# FPGA.net
KiCad netlist of a schematic drawn in Altium Designer
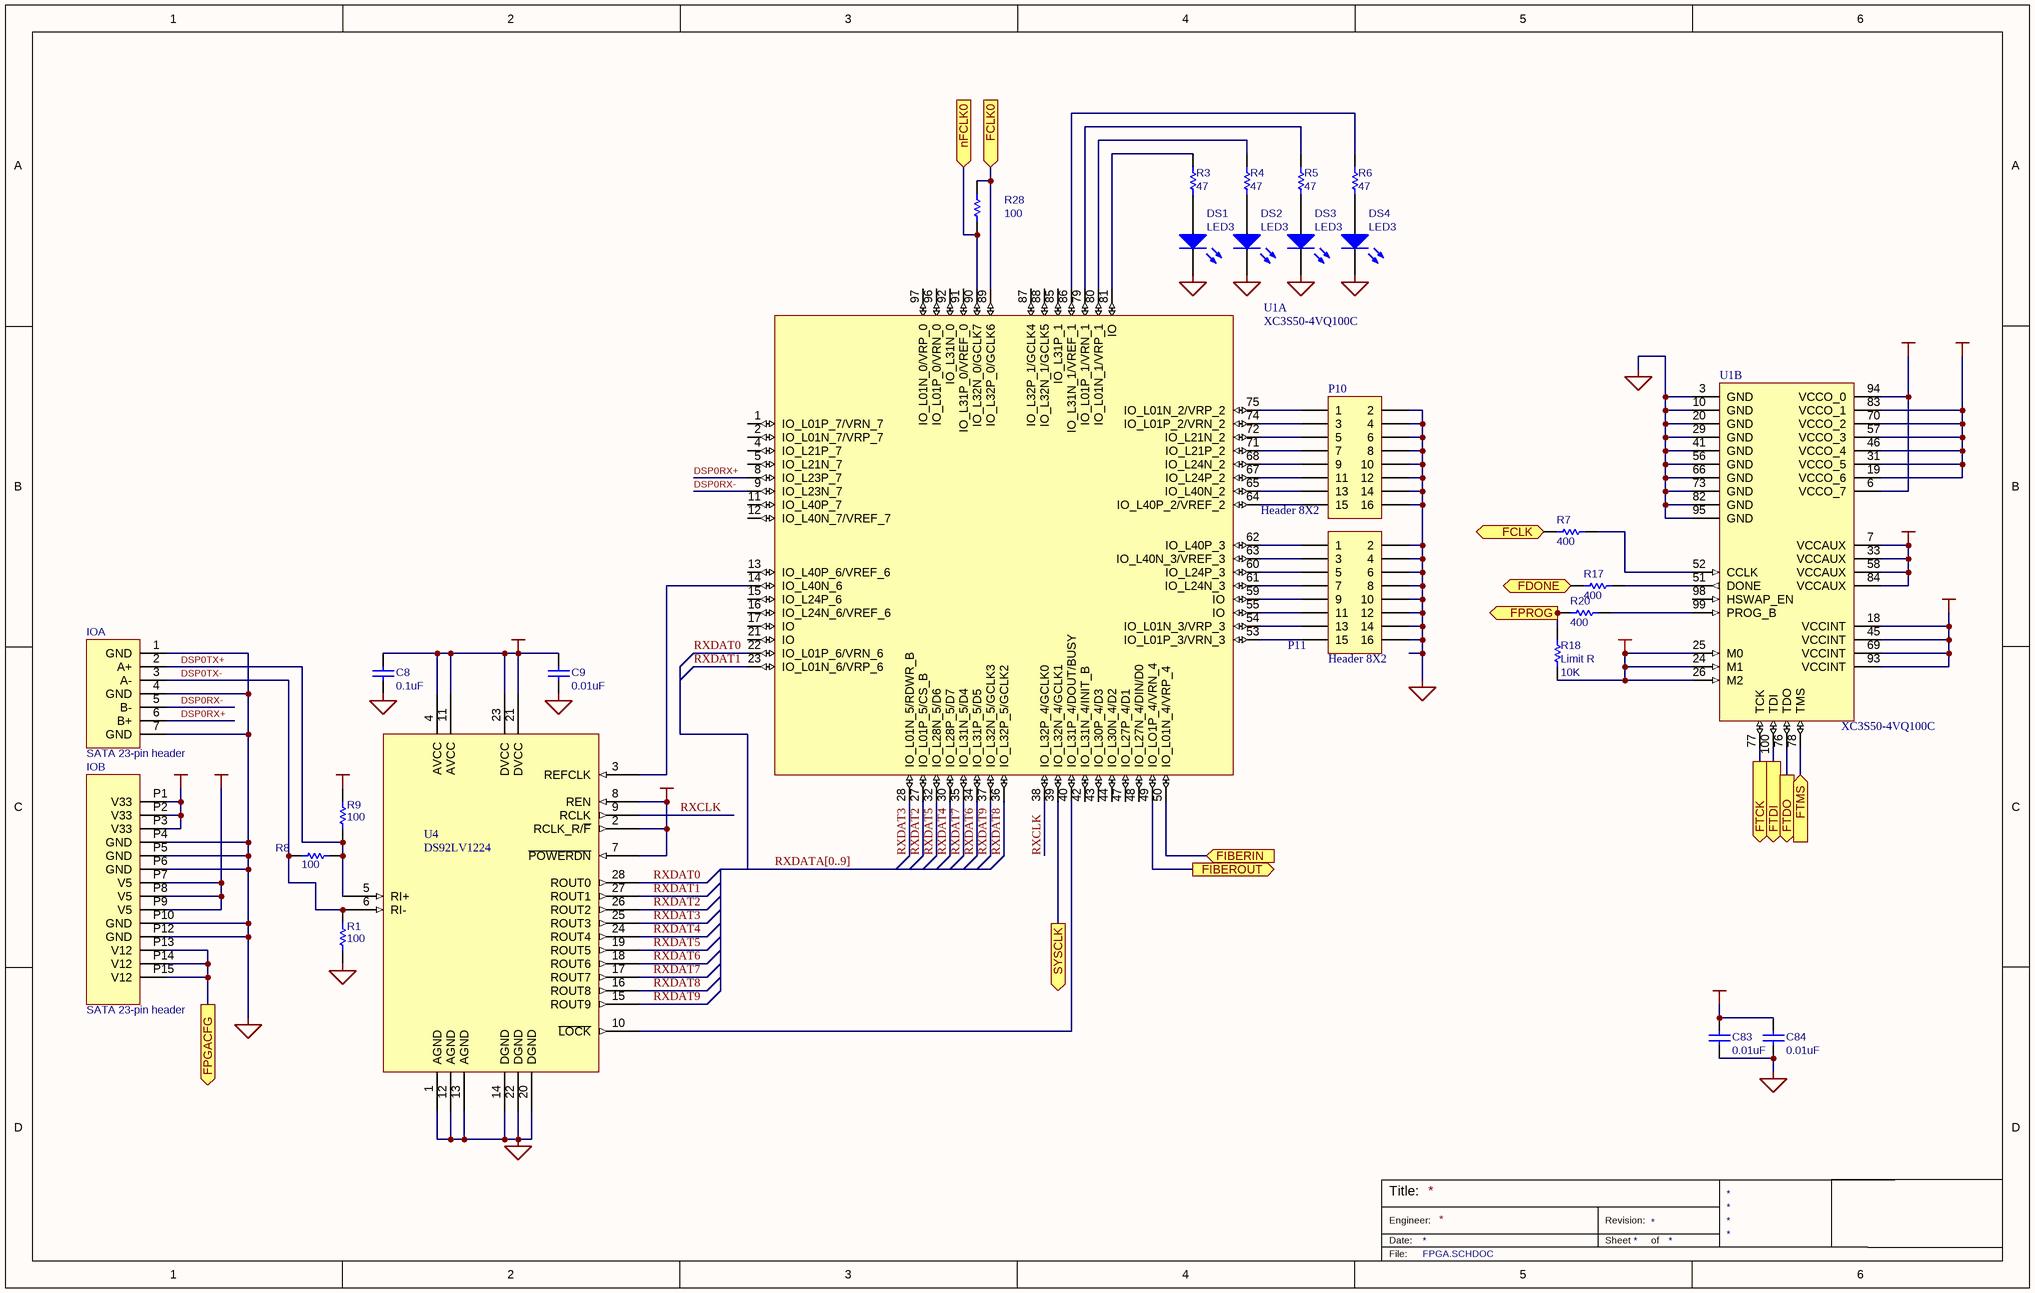
[diagram p0: FPGA.SCHDOC]

(export (version "E")
  (design (tool "Eeschema 10.0.6"))
  (components
    (comp (ref "C8")
      (value "0.1uF")
      (footprint "CC1005-0402")
      (description "Capacitor")
      (fields
        (field (name "MANUFACTURER") "Generic Components")
        (field (name "Comment") "Cap")
        (field (name "PUBLISHER") "Altium Limited")
      )
      (libsource (lib "Miscellaneous Devices") (part "Cap"))
    )
    (comp (ref "C9")
      (value "0.01uF")
      (footprint "CC1005-0402")
      (description "Capacitor")
      (fields
        (field (name "MANUFACTURER") "Generic Components")
        (field (name "Comment") "Cap")
        (field (name "PUBLISHER") "Altium Limited")
      )
      (libsource (lib "Miscellaneous Devices") (part "Cap"))
    )
    (comp (ref "C83")
      (value "0.01uF")
      (footprint "CC1005-0402")
      (description "Capacitor")
      (fields
        (field (name "MANUFACTURER") "Generic Components")
        (field (name "Comment") "Cap")
        (field (name "PUBLISHER") "Altium Limited")
      )
      (libsource (lib "Miscellaneous Devices") (part "Cap"))
    )
    (comp (ref "C84")
      (value "0.01uF")
      (footprint "CC1005-0402")
      (description "Capacitor")
      (fields
        (field (name "MANUFACTURER") "Generic Components")
        (field (name "Comment") "Cap")
        (field (name "PUBLISHER") "Altium Limited")
      )
      (libsource (lib "Miscellaneous Devices") (part "Cap"))
    )
    (comp (ref "DS1")
      (value "LED3")
      (footprint "SMD _LED")
      (description "Typical BLUE SiC LED")
      (fields (field (name "PUBLISHER") "Altium Limited"))
      (libsource (lib "Miscellaneous Devices") (part "LED3"))
    )
    (comp (ref "DS2")
      (value "LED3")
      (footprint "SMD _LED")
      (description "Typical BLUE SiC LED")
      (fields (field (name "PUBLISHER") "Altium Limited"))
      (libsource (lib "Miscellaneous Devices") (part "LED3"))
    )
    (comp (ref "DS3")
      (value "LED3")
      (footprint "SMD _LED")
      (description "Typical BLUE SiC LED")
      (fields (field (name "PUBLISHER") "Altium Limited"))
      (libsource (lib "Miscellaneous Devices") (part "LED3"))
    )
    (comp (ref "DS4")
      (value "LED3")
      (footprint "SMD _LED")
      (description "Typical BLUE SiC LED")
      (fields (field (name "PUBLISHER") "Altium Limited"))
      (libsource (lib "Miscellaneous Devices") (part "LED3"))
    )
    (comp (ref "IO")
      (value "SATA 23-pin header")
      (footprint "MOLEX 87703-0001")
      (libsource (lib "parts") (part "SATA-23"))
    )
    (comp (ref "P10")
      (value "Header 8X2")
      (footprint "HDR2X8")
      (description "Header, 8-Pin, Dual row")
      (fields (field (name "PUBLISHER") "Altium Limited"))
      (libsource (lib "Miscellaneous Connectors") (part "Header 8X2"))
    )
    (comp (ref "P11")
      (value "Header 8X2")
      (footprint "HDR2X8")
      (description "Header, 8-Pin, Dual row")
      (fields (field (name "PUBLISHER") "Altium Limited"))
      (libsource (lib "Miscellaneous Connectors") (part "Header 8X2"))
    )
    (comp (ref "R1")
      (value "100")
      (footprint "CR1005-0402")
      (description "Resistor")
      (fields (field (name "MANUFACTURER") "Generic Components") (field (name "PUBLISHER") "Altium Limited"))
      (libsource (lib "Miscellaneous Devices") (part "Res1"))
    )
    (comp (ref "R3")
      (value "47")
      (footprint "CR1608-0603")
      (description "Resistor")
      (fields
        (field (name "MANUFACTURER") "Generic Components")
        (field (name "Comment") "Res1")
        (field (name "PUBLISHER") "Altium Limited")
      )
      (libsource (lib "Miscellaneous Devices") (part "Res1"))
    )
    (comp (ref "R4")
      (value "47")
      (footprint "CR1608-0603")
      (description "Resistor")
      (fields
        (field (name "MANUFACTURER") "Generic Components")
        (field (name "Comment") "Res1")
        (field (name "PUBLISHER") "Altium Limited")
      )
      (libsource (lib "Miscellaneous Devices") (part "Res1"))
    )
    (comp (ref "R5")
      (value "47")
      (footprint "CR1608-0603")
      (description "Resistor")
      (fields
        (field (name "MANUFACTURER") "Generic Components")
        (field (name "Comment") "Res1")
        (field (name "PUBLISHER") "Altium Limited")
      )
      (libsource (lib "Miscellaneous Devices") (part "Res1"))
    )
    (comp (ref "R6")
      (value "47")
      (footprint "CR1608-0603")
      (description "Resistor")
      (fields
        (field (name "MANUFACTURER") "Generic Components")
        (field (name "Comment") "Res1")
        (field (name "PUBLISHER") "Altium Limited")
      )
      (libsource (lib "Miscellaneous Devices") (part "Res1"))
    )
    (comp (ref "R7")
      (value "400")
      (footprint "CR1608-0603")
      (description "Resistor")
      (fields (field (name "Comment") "Res1") (field (name "PUBLISHER") "Altium Limited"))
      (libsource (lib "Miscellaneous Devices") (part "Res1"))
    )
    (comp (ref "R8")
      (value "100")
      (footprint "CR1005-0402")
      (description "Resistor")
      (fields (field (name "MANUFACTURER") "Generic Components") (field (name "PUBLISHER") "Altium Limited"))
      (libsource (lib "Miscellaneous Devices") (part "Res1"))
    )
    (comp (ref "R9")
      (value "100")
      (footprint "CR1005-0402")
      (description "Resistor")
      (fields (field (name "MANUFACTURER") "Generic Components") (field (name "PUBLISHER") "Altium Limited"))
      (libsource (lib "Miscellaneous Devices") (part "Res1"))
    )
    (comp (ref "R17")
      (value "400")
      (footprint "CR1608-0603")
      (description "Resistor")
      (fields (field (name "Comment") "Res1") (field (name "PUBLISHER") "Altium Limited"))
      (libsource (lib "Miscellaneous Devices") (part "Res1"))
    )
    (comp (ref "R18")
      (value "Limit R")
      (footprint "CR1608-0603")
      (description "Resistor")
      (fields
        (field (name "MANUFACTURER") "Generic Components")
        (field (name "ALTIUM_VALUE") "10K")
        (field (name "PUBLISHER") "Altium Limited")
      )
      (libsource (lib "Miscellaneous Devices") (part "Res1"))
    )
    (comp (ref "R20")
      (value "400")
      (footprint "CR1608-0603")
      (description "Resistor")
      (fields (field (name "Comment") "Res1") (field (name "PUBLISHER") "Altium Limited"))
      (libsource (lib "Miscellaneous Devices") (part "Res1"))
    )
    (comp (ref "R28")
      (value "100")
      (footprint "CR1005-0402")
      (description "Resistor")
      (fields (field (name "MANUFACTURER") "Generic Components") (field (name "PUBLISHER") "Altium Limited"))
      (libsource (lib "Miscellaneous Devices") (part "Res1"))
    )
    (comp (ref "U1")
      (value "XC3S50-4VQ100C")
      (footprint "Xilinx TQ100")
      (description "Xilinx Spartan-3 VQ100")
      (libsource (lib "parts") (part "XC3S50-4VQ100C"))
    )
    (comp (ref "U4")
      (value "DS92LV1224")
      (footprint "SSO-G28/E4.3")
      (description "30-66 MHz 10-Bit Bus LVDS Deserializer")
      (libsource (lib "parts") (part "DS92LV1224"))
    )
  )
  (nets
    (net (code "11") (name "+1.2VCC") (class "Default")
      (node (ref "U1") (pin "18") (pinfunction "VCCINT_18") (pintype "power_in"))
      (node (ref "U1") (pin "45") (pinfunction "VCCINT_45") (pintype "power_in"))
      (node (ref "U1") (pin "69") (pinfunction "VCCINT_69") (pintype "power_in"))
      (node (ref "U1") (pin "93") (pinfunction "VCCINT_93") (pintype "power_in"))
    )
    (net (code "12") (name "+2.5VCC") (class "Default")
      (node (ref "U1") (pin "33") (pinfunction "VCCAUX_33") (pintype "power_in"))
      (node (ref "U1") (pin "58") (pinfunction "VCCAUX_58") (pintype "power_in"))
      (node (ref "U1") (pin "6") (pinfunction "VCCO_7_6") (pintype "power_in"))
      (node (ref "U1") (pin "7") (pinfunction "VCCAUX_7") (pintype "power_in"))
      (node (ref "U1") (pin "84") (pinfunction "VCCAUX_84") (pintype "power_in"))
      (node (ref "U1") (pin "94") (pinfunction "VCCO_0_94") (pintype "power_in"))
    )
    (net (code "13") (name "+5VCC") (class "Default")
      (node (ref "IO") (pin "P7") (pinfunction "V5_P7") (pintype "passive"))
      (node (ref "IO") (pin "P8") (pinfunction "V5_P8") (pintype "passive"))
      (node (ref "IO") (pin "P9") (pinfunction "V5_P9") (pintype "passive"))
    )
    (net (code "14") (name "/DSP0RX+") (class "Default")
      (node (ref "IO") (pin "6") (pinfunction "B+_6") (pintype "passive"))
      (node (ref "U1") (pin "8") (pinfunction "IO_L23P_7_8") (pintype "bidirectional"))
    )
    (net (code "15") (name "/DSP0RX-") (class "Default")
      (node (ref "IO") (pin "5") (pinfunction "B-_5") (pintype "passive"))
      (node (ref "U1") (pin "9") (pinfunction "IO_L23N_7_9") (pintype "bidirectional"))
    )
    (net (code "16") (name "/DSP0TX+") (class "Default")
      (node (ref "IO") (pin "2") (pinfunction "A+_2") (pintype "passive"))
      (node (ref "R8") (pin "2") (pinfunction "2_2") (pintype "passive"))
      (node (ref "R9") (pin "2") (pinfunction "2_2") (pintype "passive"))
      (node (ref "U4") (pin "5") (pinfunction "RI+_5") (pintype "input"))
    )
    (net (code "17") (name "/DSP0TX-") (class "Default")
      (node (ref "IO") (pin "3") (pinfunction "A-_3") (pintype "passive"))
      (node (ref "R1") (pin "2") (pinfunction "2_2") (pintype "passive"))
      (node (ref "R8") (pin "1") (pinfunction "1_1") (pintype "passive"))
      (node (ref "U4") (pin "6") (pinfunction "RI-_6") (pintype "input"))
    )
    (net (code "18") (name "/FCLK") (class "Default")
      (node (ref "R7") (pin "2") (pinfunction "2_2") (pintype "passive"))
    )
    (net (code "19") (name "/FCLK0") (class "Default")
      (node (ref "R28") (pin "2") (pinfunction "2_2") (pintype "passive"))
      (node (ref "U1") (pin "89") (pinfunction "IO_L32P_0/GCLK6_89") (pintype "bidirectional"))
    )
    (net (code "20") (name "/FDONE") (class "Default")
      (node (ref "R17") (pin "2") (pinfunction "2_2") (pintype "passive"))
    )
    (net (code "21") (name "/FIBERIN") (class "Default")
      (node (ref "U1") (pin "50") (pinfunction "IO_L01N_4/VRP_4_50") (pintype "bidirectional"))
    )
    (net (code "22") (name "/FIBEROUT") (class "Default")
      (node (ref "U1") (pin "49") (pinfunction "IO_LO1P_4/VRN_4_49") (pintype "bidirectional"))
    )
    (net (code "23") (name "/FPGACFG") (class "Default")
      (node (ref "IO") (pin "P13") (pinfunction "V12_P13") (pintype "passive"))
      (node (ref "IO") (pin "P14") (pinfunction "V12_P14") (pintype "passive"))
      (node (ref "IO") (pin "P15") (pinfunction "V12_P15") (pintype "passive"))
    )
    (net (code "24") (name "/FPROG") (class "Default")
      (node (ref "R18") (pin "1") (pinfunction "1_1") (pintype "passive"))
      (node (ref "R20") (pin "2") (pinfunction "2_2") (pintype "passive"))
    )
    (net (code "25") (name "/FTCK") (class "Default")
      (node (ref "U1") (pin "77") (pinfunction "TCK_77") (pintype "bidirectional"))
    )
    (net (code "26") (name "/FTDI") (class "Default")
      (node (ref "U1") (pin "100") (pinfunction "TDI_100") (pintype "bidirectional"))
    )
    (net (code "27") (name "/FTDO") (class "Default")
      (node (ref "U1") (pin "76") (pinfunction "TDO_76") (pintype "bidirectional"))
    )
    (net (code "28") (name "/FTMS") (class "Default")
      (node (ref "U1") (pin "78") (pinfunction "TMS_78") (pintype "bidirectional"))
    )
    (net (code "29") (name "/RXCLK") (class "Default")
      (node (ref "U1") (pin "38") (pinfunction "IO_L32P_4/GCLK0_38") (pintype "bidirectional"))
      (node (ref "U4") (pin "9") (pinfunction "RCLK_9") (pintype "output"))
    )
    (net (code "30") (name "/RXDAT0") (class "Default")
      (node (ref "U1") (pin "22") (pinfunction "IO_L01P_6/VRN_6_22") (pintype "bidirectional"))
      (node (ref "U4") (pin "28") (pinfunction "ROUT0_28") (pintype "output"))
    )
    (net (code "31") (name "/RXDAT1") (class "Default")
      (node (ref "U1") (pin "23") (pinfunction "IO_L01N_6/VRP_6_23") (pintype "bidirectional"))
      (node (ref "U4") (pin "27") (pinfunction "ROUT1_27") (pintype "output"))
    )
    (net (code "32") (name "/RXDAT2") (class "Default")
      (node (ref "U1") (pin "27") (pinfunction "IO_L01P_5/CS_B_27") (pintype "bidirectional"))
      (node (ref "U4") (pin "26") (pinfunction "ROUT2_26") (pintype "output"))
    )
    (net (code "33") (name "/RXDAT3") (class "Default")
      (node (ref "U1") (pin "28") (pinfunction "IO_L01N_5/RDWR_B_28") (pintype "bidirectional"))
      (node (ref "U4") (pin "25") (pinfunction "ROUT3_25") (pintype "output"))
    )
    (net (code "34") (name "/RXDAT4") (class "Default")
      (node (ref "U1") (pin "30") (pinfunction "IO_L28P_5/D7_30") (pintype "bidirectional"))
      (node (ref "U4") (pin "24") (pinfunction "ROUT4_24") (pintype "output"))
    )
    (net (code "35") (name "/RXDAT5") (class "Default")
      (node (ref "U1") (pin "32") (pinfunction "IO_L28N_5/D6_32") (pintype "bidirectional"))
      (node (ref "U4") (pin "19") (pinfunction "ROUT5_19") (pintype "output"))
    )
    (net (code "36") (name "/RXDAT6") (class "Default")
      (node (ref "U1") (pin "34") (pinfunction "IO_L31P_5/D5_34") (pintype "bidirectional"))
      (node (ref "U4") (pin "18") (pinfunction "ROUT6_18") (pintype "output"))
    )
    (net (code "37") (name "/RXDAT7") (class "Default")
      (node (ref "U1") (pin "35") (pinfunction "IO_L31N_5/D4_35") (pintype "bidirectional"))
      (node (ref "U4") (pin "17") (pinfunction "ROUT7_17") (pintype "output"))
    )
    (net (code "38") (name "/RXDAT8") (class "Default")
      (node (ref "U1") (pin "36") (pinfunction "IO_L32P_5/GCLK2_36") (pintype "bidirectional"))
      (node (ref "U4") (pin "16") (pinfunction "ROUT8_16") (pintype "output"))
    )
    (net (code "39") (name "/RXDAT9") (class "Default")
      (node (ref "U1") (pin "37") (pinfunction "IO_L32N_5/GCLK3_37") (pintype "bidirectional"))
      (node (ref "U4") (pin "15") (pinfunction "ROUT9_15") (pintype "output"))
    )
    (net (code "41") (name "/SYSCLK") (class "Default")
      (node (ref "U1") (pin "39") (pinfunction "IO_L32N_4/GCLK1_39") (pintype "bidirectional"))
    )
    (net (code "42") (name "/nFCLK0") (class "Default")
      (node (ref "R28") (pin "1") (pinfunction "1_1") (pintype "passive"))
      (node (ref "U1") (pin "90") (pinfunction "IO_L32N_0/GCLK7_90") (pintype "bidirectional"))
    )
    (net (code "43") (name "GND") (class "Default")
      (node (ref "C8") (pin "1") (pinfunction "1_1") (pintype "passive"))
      (node (ref "C83") (pin "1") (pinfunction "1_1") (pintype "passive"))
      (node (ref "C84") (pin "1") (pinfunction "1_1") (pintype "passive"))
      (node (ref "C9") (pin "1") (pinfunction "1_1") (pintype "passive"))
      (node (ref "DS1") (pin "2") (pinfunction "K_2") (pintype "passive"))
      (node (ref "DS2") (pin "2") (pinfunction "K_2") (pintype "passive"))
      (node (ref "DS3") (pin "2") (pinfunction "K_2") (pintype "passive"))
      (node (ref "DS4") (pin "2") (pinfunction "K_2") (pintype "passive"))
      (node (ref "IO") (pin "1") (pinfunction "GND_1") (pintype "passive"))
      (node (ref "IO") (pin "4") (pinfunction "GND_4") (pintype "passive"))
      (node (ref "IO") (pin "7") (pinfunction "GND_7") (pintype "passive"))
      (node (ref "IO") (pin "P10") (pinfunction "GND_P10") (pintype "passive"))
      (node (ref "IO") (pin "P12") (pinfunction "GND_P12") (pintype "passive"))
      (node (ref "IO") (pin "P4") (pinfunction "GND_P4") (pintype "passive"))
      (node (ref "IO") (pin "P5") (pinfunction "GND_P5") (pintype "passive"))
      (node (ref "IO") (pin "P6") (pinfunction "GND_P6") (pintype "passive"))
      (node (ref "P10") (pin "10") (pinfunction "10_10") (pintype "passive"))
      (node (ref "P10") (pin "12") (pinfunction "12_12") (pintype "passive"))
      (node (ref "P10") (pin "14") (pinfunction "14_14") (pintype "passive"))
      (node (ref "P10") (pin "16") (pinfunction "16_16") (pintype "passive"))
      (node (ref "P10") (pin "2") (pinfunction "2_2") (pintype "passive"))
      (node (ref "P10") (pin "4") (pinfunction "4_4") (pintype "passive"))
      (node (ref "P10") (pin "6") (pinfunction "6_6") (pintype "passive"))
      (node (ref "P10") (pin "8") (pinfunction "8_8") (pintype "passive"))
      (node (ref "P11") (pin "10") (pinfunction "10_10") (pintype "passive"))
      (node (ref "P11") (pin "12") (pinfunction "12_12") (pintype "passive"))
      (node (ref "P11") (pin "14") (pinfunction "14_14") (pintype "passive"))
      (node (ref "P11") (pin "16") (pinfunction "16_16") (pintype "passive"))
      (node (ref "P11") (pin "2") (pinfunction "2_2") (pintype "passive"))
      (node (ref "P11") (pin "4") (pinfunction "4_4") (pintype "passive"))
      (node (ref "P11") (pin "6") (pinfunction "6_6") (pintype "passive"))
      (node (ref "P11") (pin "8") (pinfunction "8_8") (pintype "passive"))
      (node (ref "R1") (pin "1") (pinfunction "1_1") (pintype "passive"))
      (node (ref "U1") (pin "10") (pinfunction "GND_10") (pintype "power_in"))
      (node (ref "U1") (pin "20") (pinfunction "GND_20") (pintype "power_in"))
      (node (ref "U1") (pin "29") (pinfunction "GND_29") (pintype "power_in"))
      (node (ref "U1") (pin "3") (pinfunction "GND_3") (pintype "power_in"))
      (node (ref "U1") (pin "41") (pinfunction "GND_41") (pintype "power_in"))
      (node (ref "U1") (pin "56") (pinfunction "GND_56") (pintype "power_in"))
      (node (ref "U1") (pin "66") (pinfunction "GND_66") (pintype "power_in"))
      (node (ref "U1") (pin "73") (pinfunction "GND_73") (pintype "power_in"))
      (node (ref "U1") (pin "82") (pinfunction "GND_82") (pintype "power_in"))
      (node (ref "U1") (pin "95") (pinfunction "GND_95") (pintype "power_in"))
      (node (ref "U4") (pin "1") (pinfunction "AGND_1") (pintype "power_in"))
      (node (ref "U4") (pin "12") (pinfunction "AGND_12") (pintype "power_in"))
      (node (ref "U4") (pin "13") (pinfunction "AGND_13") (pintype "power_in"))
      (node (ref "U4") (pin "14") (pinfunction "DGND_14") (pintype "power_in"))
      (node (ref "U4") (pin "20") (pinfunction "DGND_20") (pintype "power_in"))
      (node (ref "U4") (pin "22") (pinfunction "DGND_22") (pintype "power_in"))
    )
    (net (code "44") (name "Net-(DS1-A)") (class "Default")
      (node (ref "DS1") (pin "1") (pinfunction "A_1") (pintype "passive"))
      (node (ref "R3") (pin "2") (pinfunction "2_2") (pintype "passive"))
    )
    (net (code "45") (name "Net-(DS2-A)") (class "Default")
      (node (ref "DS2") (pin "1") (pinfunction "A_1") (pintype "passive"))
      (node (ref "R4") (pin "2") (pinfunction "2_2") (pintype "passive"))
    )
    (net (code "46") (name "Net-(DS3-A)") (class "Default")
      (node (ref "DS3") (pin "1") (pinfunction "A_1") (pintype "passive"))
      (node (ref "R5") (pin "2") (pinfunction "2_2") (pintype "passive"))
    )
    (net (code "47") (name "Net-(DS4-A)") (class "Default")
      (node (ref "DS4") (pin "1") (pinfunction "A_1") (pintype "passive"))
      (node (ref "R6") (pin "2") (pinfunction "2_2") (pintype "passive"))
    )
    (net (code "48") (name "Net-(P11-Pad9)") (class "Default")
      (node (ref "P11") (pin "9") (pinfunction "9_9") (pintype "passive"))
      (node (ref "U1") (pin "59") (pinfunction "IO_59") (pintype "bidirectional"))
    )
    (net (code "49") (name "Net-(P11-Pad11)") (class "Default")
      (node (ref "P11") (pin "11") (pinfunction "11_11") (pintype "passive"))
      (node (ref "U1") (pin "55") (pinfunction "IO_55") (pintype "bidirectional"))
    )
    (net (code "50") (name "Net-(R3-Pad1)") (class "Default")
      (node (ref "R3") (pin "1") (pinfunction "1_1") (pintype "passive"))
      (node (ref "U1") (pin "81") (pinfunction "IO_81") (pintype "bidirectional"))
    )
    (net (code "51") (name "Net-(U1A-IO_L01N_1{slash}VRP_1)") (class "Default")
      (node (ref "R4") (pin "1") (pinfunction "1_1") (pintype "passive"))
      (node (ref "U1") (pin "80") (pinfunction "IO_L01N_1/VRP_1_80") (pintype "bidirectional"))
    )
    (net (code "52") (name "Net-(U1A-IO_L01N_2{slash}VRP_2)") (class "Default")
      (node (ref "P10") (pin "1") (pinfunction "1_1") (pintype "passive"))
      (node (ref "U1") (pin "75") (pinfunction "IO_L01N_2/VRP_2_75") (pintype "bidirectional"))
    )
    (net (code "53") (name "Net-(U1A-IO_L01N_3{slash}VRP_3)") (class "Default")
      (node (ref "P11") (pin "13") (pinfunction "13_13") (pintype "passive"))
      (node (ref "U1") (pin "54") (pinfunction "IO_L01N_3/VRP_3_54") (pintype "bidirectional"))
    )
    (net (code "54") (name "Net-(U1A-IO_L01P_1{slash}VRN_1)") (class "Default")
      (node (ref "R5") (pin "1") (pinfunction "1_1") (pintype "passive"))
      (node (ref "U1") (pin "79") (pinfunction "IO_L01P_1/VRN_1_79") (pintype "bidirectional"))
    )
    (net (code "55") (name "Net-(U1A-IO_L01P_2{slash}VRN_2)") (class "Default")
      (node (ref "P10") (pin "3") (pinfunction "3_3") (pintype "passive"))
      (node (ref "U1") (pin "74") (pinfunction "IO_L01P_2/VRN_2_74") (pintype "bidirectional"))
    )
    (net (code "56") (name "Net-(U1A-IO_L01P_3{slash}VRN_3)") (class "Default")
      (node (ref "P11") (pin "15") (pinfunction "15_15") (pintype "passive"))
      (node (ref "U1") (pin "53") (pinfunction "IO_L01P_3/VRN_3_53") (pintype "bidirectional"))
    )
    (net (code "57") (name "Net-(U1A-IO_L21N_2)") (class "Default")
      (node (ref "P10") (pin "5") (pinfunction "5_5") (pintype "passive"))
      (node (ref "U1") (pin "72") (pinfunction "IO_L21N_2_72") (pintype "bidirectional"))
    )
    (net (code "58") (name "Net-(U1A-IO_L21P_2)") (class "Default")
      (node (ref "P10") (pin "7") (pinfunction "7_7") (pintype "passive"))
      (node (ref "U1") (pin "71") (pinfunction "IO_L21P_2_71") (pintype "bidirectional"))
    )
    (net (code "59") (name "Net-(U1A-IO_L24N_2)") (class "Default")
      (node (ref "P10") (pin "9") (pinfunction "9_9") (pintype "passive"))
      (node (ref "U1") (pin "68") (pinfunction "IO_L24N_2_68") (pintype "bidirectional"))
    )
    (net (code "60") (name "Net-(U1A-IO_L24N_3)") (class "Default")
      (node (ref "P11") (pin "7") (pinfunction "7_7") (pintype "passive"))
      (node (ref "U1") (pin "61") (pinfunction "IO_L24N_3_61") (pintype "bidirectional"))
    )
    (net (code "61") (name "Net-(U1A-IO_L24P_2)") (class "Default")
      (node (ref "P10") (pin "11") (pinfunction "11_11") (pintype "passive"))
      (node (ref "U1") (pin "67") (pinfunction "IO_L24P_2_67") (pintype "bidirectional"))
    )
    (net (code "62") (name "Net-(U1A-IO_L24P_3)") (class "Default")
      (node (ref "P11") (pin "5") (pinfunction "5_5") (pintype "passive"))
      (node (ref "U1") (pin "60") (pinfunction "IO_L24P_3_60") (pintype "bidirectional"))
    )
    (net (code "63") (name "Net-(U1A-IO_L31N_1{slash}VREF_1)") (class "Default")
      (node (ref "R6") (pin "1") (pinfunction "1_1") (pintype "passive"))
      (node (ref "U1") (pin "86") (pinfunction "IO_L31N_1/VREF_1_86") (pintype "bidirectional"))
    )
    (net (code "64") (name "Net-(U1A-IO_L31P_4{slash}DOUT{slash}BUSY)") (class "Default")
      (node (ref "U1") (pin "40") (pinfunction "IO_L31P_4/DOUT/BUSY_40") (pintype "bidirectional"))
      (node (ref "U4") (pin "10") (pinfunction "~{LOCK}_10") (pintype "output"))
    )
    (net (code "65") (name "Net-(U1A-IO_L40N_2)") (class "Default")
      (node (ref "P10") (pin "13") (pinfunction "13_13") (pintype "passive"))
      (node (ref "U1") (pin "65") (pinfunction "IO_L40N_2_65") (pintype "bidirectional"))
    )
    (net (code "66") (name "Net-(U1A-IO_L40N_3{slash}VREF_3)") (class "Default")
      (node (ref "P11") (pin "3") (pinfunction "3_3") (pintype "passive"))
      (node (ref "U1") (pin "63") (pinfunction "IO_L40N_3/VREF_3_63") (pintype "bidirectional"))
    )
    (net (code "67") (name "Net-(U1A-IO_L40N_6)") (class "Default")
      (node (ref "U1") (pin "14") (pinfunction "IO_L40N_6_14") (pintype "bidirectional"))
      (node (ref "U4") (pin "3") (pinfunction "REFCLK_3") (pintype "input"))
    )
    (net (code "68") (name "Net-(U1A-IO_L40P_2{slash}VREF_2)") (class "Default")
      (node (ref "P10") (pin "15") (pinfunction "15_15") (pintype "passive"))
      (node (ref "U1") (pin "64") (pinfunction "IO_L40P_2/VREF_2_64") (pintype "bidirectional"))
    )
    (net (code "69") (name "Net-(U1A-IO_L40P_3)") (class "Default")
      (node (ref "P11") (pin "1") (pinfunction "1_1") (pintype "passive"))
      (node (ref "U1") (pin "62") (pinfunction "IO_L40P_3_62") (pintype "bidirectional"))
    )
    (net (code "70") (name "Net-(U1B-CCLK)") (class "Default")
      (node (ref "R7") (pin "1") (pinfunction "1_1") (pintype "passive"))
      (node (ref "U1") (pin "52") (pinfunction "CCLK_52") (pintype "input"))
    )
    (net (code "71") (name "Net-(U1B-DONE)") (class "Default")
      (node (ref "R17") (pin "1") (pinfunction "1_1") (pintype "passive"))
      (node (ref "U1") (pin "51") (pinfunction "DONE_51") (pintype "output"))
    )
    (net (code "72") (name "Net-(U1B-PROG_B)") (class "Default")
      (node (ref "R20") (pin "1") (pinfunction "1_1") (pintype "passive"))
      (node (ref "U1") (pin "99") (pinfunction "PROG_B_99") (pintype "input"))
    )
    (net (code "73") (name "VCC") (class "Default")
      (node (ref "C8") (pin "2") (pinfunction "2_2") (pintype "passive"))
      (node (ref "C83") (pin "2") (pinfunction "2_2") (pintype "passive"))
      (node (ref "C84") (pin "2") (pinfunction "2_2") (pintype "passive"))
      (node (ref "C9") (pin "2") (pinfunction "2_2") (pintype "passive"))
      (node (ref "IO") (pin "P1") (pinfunction "V33_P1") (pintype "passive"))
      (node (ref "IO") (pin "P2") (pinfunction "V33_P2") (pintype "passive"))
      (node (ref "IO") (pin "P3") (pinfunction "V33_P3") (pintype "passive"))
      (node (ref "R18") (pin "2") (pinfunction "2_2") (pintype "passive"))
      (node (ref "R9") (pin "1") (pinfunction "1_1") (pintype "passive"))
      (node (ref "U1") (pin "19") (pinfunction "VCCO_6_19") (pintype "power_in"))
      (node (ref "U1") (pin "24") (pinfunction "M1_24") (pintype "input"))
      (node (ref "U1") (pin "25") (pinfunction "M0_25") (pintype "input"))
      (node (ref "U1") (pin "26") (pinfunction "M2_26") (pintype "input"))
      (node (ref "U1") (pin "31") (pinfunction "VCCO_5_31") (pintype "power_in"))
      (node (ref "U1") (pin "46") (pinfunction "VCCO_4_46") (pintype "power_in"))
      (node (ref "U1") (pin "57") (pinfunction "VCCO_3_57") (pintype "power_in"))
      (node (ref "U1") (pin "70") (pinfunction "VCCO_2_70") (pintype "power_in"))
      (node (ref "U1") (pin "83") (pinfunction "VCCO_1_83") (pintype "power_in"))
      (node (ref "U4") (pin "11") (pinfunction "AVCC_11") (pintype "power_in"))
      (node (ref "U4") (pin "2") (pinfunction "RCLK_R/~{F}_2") (pintype "output"))
      (node (ref "U4") (pin "21") (pinfunction "DVCC_21") (pintype "power_in"))
      (node (ref "U4") (pin "23") (pinfunction "DVCC_23") (pintype "power_in"))
      (node (ref "U4") (pin "4") (pinfunction "AVCC_4") (pintype "power_in"))
      (node (ref "U4") (pin "7") (pinfunction "~{POWERDN}_7") (pintype "input"))
      (node (ref "U4") (pin "8") (pinfunction "REN_8") (pintype "input"))
    )
    (net (code "74") (name "unconnected-(U1A-IO-Pad17)") (class "Default")
      (node (ref "U1") (pin "17") (pinfunction "IO_17") (pintype "bidirectional"))
    )
    (net (code "75") (name "unconnected-(U1A-IO-Pad21)") (class "Default")
      (node (ref "U1") (pin "21") (pinfunction "IO_21") (pintype "bidirectional"))
    )
    (net (code "76") (name "unconnected-(U1A-IO_L01N_0{slash}VRP_0-Pad97)") (class "Default")
      (node (ref "U1") (pin "97") (pinfunction "IO_L01N_0/VRP_0_97") (pintype "bidirectional"))
    )
    (net (code "77") (name "unconnected-(U1A-IO_L01N_7{slash}VRP_7-Pad2)") (class "Default")
      (node (ref "U1") (pin "2") (pinfunction "IO_L01N_7/VRP_7_2") (pintype "bidirectional"))
    )
    (net (code "78") (name "unconnected-(U1A-IO_L01P_0{slash}VRN_0-Pad96)") (class "Default")
      (node (ref "U1") (pin "96") (pinfunction "IO_L01P_0/VRN_0_96") (pintype "bidirectional"))
    )
    (net (code "79") (name "unconnected-(U1A-IO_L01P_7{slash}VRN_7-Pad1)") (class "Default")
      (node (ref "U1") (pin "1") (pinfunction "IO_L01P_7/VRN_7_1") (pintype "bidirectional"))
    )
    (net (code "80") (name "unconnected-(U1A-IO_L21N_7-Pad5)") (class "Default")
      (node (ref "U1") (pin "5") (pinfunction "IO_L21N_7_5") (pintype "bidirectional"))
    )
    (net (code "81") (name "unconnected-(U1A-IO_L21P_7-Pad4)") (class "Default")
      (node (ref "U1") (pin "4") (pinfunction "IO_L21P_7_4") (pintype "bidirectional"))
    )
    (net (code "82") (name "unconnected-(U1A-IO_L24N_6{slash}VREF_6-Pad16)") (class "Default")
      (node (ref "U1") (pin "16") (pinfunction "IO_L24N_6/VREF_6_16") (pintype "bidirectional"))
    )
    (net (code "83") (name "unconnected-(U1A-IO_L24P_6-Pad15)") (class "Default")
      (node (ref "U1") (pin "15") (pinfunction "IO_L24P_6_15") (pintype "bidirectional"))
    )
    (net (code "84") (name "unconnected-(U1A-IO_L27N_4{slash}DIN{slash}D0-Pad48)") (class "Default")
      (node (ref "U1") (pin "48") (pinfunction "IO_L27N_4/DIN/D0_48") (pintype "bidirectional"))
    )
    (net (code "85") (name "unconnected-(U1A-IO_L27P_4{slash}D1-Pad47)") (class "Default")
      (node (ref "U1") (pin "47") (pinfunction "IO_L27P_4/D1_47") (pintype "bidirectional"))
    )
    (net (code "86") (name "unconnected-(U1A-IO_L30N_4{slash}D2-Pad44)") (class "Default")
      (node (ref "U1") (pin "44") (pinfunction "IO_L30N_4/D2_44") (pintype "bidirectional"))
    )
    (net (code "87") (name "unconnected-(U1A-IO_L30P_4{slash}D3-Pad43)") (class "Default")
      (node (ref "U1") (pin "43") (pinfunction "IO_L30P_4/D3_43") (pintype "bidirectional"))
    )
    (net (code "88") (name "unconnected-(U1A-IO_L31N_0-Pad92)") (class "Default")
      (node (ref "U1") (pin "92") (pinfunction "IO_L31N_0_92") (pintype "bidirectional"))
    )
    (net (code "89") (name "unconnected-(U1A-IO_L31N_4{slash}INIT_B-Pad42)") (class "Default")
      (node (ref "U1") (pin "42") (pinfunction "IO_L31N_4/INIT_B_42") (pintype "bidirectional"))
    )
    (net (code "90") (name "unconnected-(U1A-IO_L31P_0{slash}VREF_0-Pad91)") (class "Default")
      (node (ref "U1") (pin "91") (pinfunction "IO_L31P_0/VREF_0_91") (pintype "bidirectional"))
    )
    (net (code "91") (name "unconnected-(U1A-IO_L31P_1-Pad85)") (class "Default")
      (node (ref "U1") (pin "85") (pinfunction "IO_L31P_1_85") (pintype "bidirectional"))
    )
    (net (code "92") (name "unconnected-(U1A-IO_L32N_1{slash}GCLK5-Pad88)") (class "Default")
      (node (ref "U1") (pin "88") (pinfunction "IO_L32N_1/GCLK5_88") (pintype "bidirectional"))
    )
    (net (code "93") (name "unconnected-(U1A-IO_L32P_1{slash}GCLK4-Pad87)") (class "Default")
      (node (ref "U1") (pin "87") (pinfunction "IO_L32P_1/GCLK4_87") (pintype "bidirectional"))
    )
    (net (code "94") (name "unconnected-(U1A-IO_L40N_7{slash}VREF_7-Pad12)") (class "Default")
      (node (ref "U1") (pin "12") (pinfunction "IO_L40N_7/VREF_7_12") (pintype "bidirectional"))
    )
    (net (code "95") (name "unconnected-(U1A-IO_L40P_6{slash}VREF_6-Pad13)") (class "Default")
      (node (ref "U1") (pin "13") (pinfunction "IO_L40P_6/VREF_6_13") (pintype "bidirectional"))
    )
    (net (code "96") (name "unconnected-(U1A-IO_L40P_7-Pad11)") (class "Default")
      (node (ref "U1") (pin "11") (pinfunction "IO_L40P_7_11") (pintype "bidirectional"))
    )
    (net (code "97") (name "unconnected-(U1B-HSWAP_EN-Pad98)") (class "Default")
      (node (ref "U1") (pin "98") (pinfunction "HSWAP_EN_98") (pintype "input"))
    )
  )
)
